# battery_controller.net
KiCad netlist of a schematic drawn in EAGLE
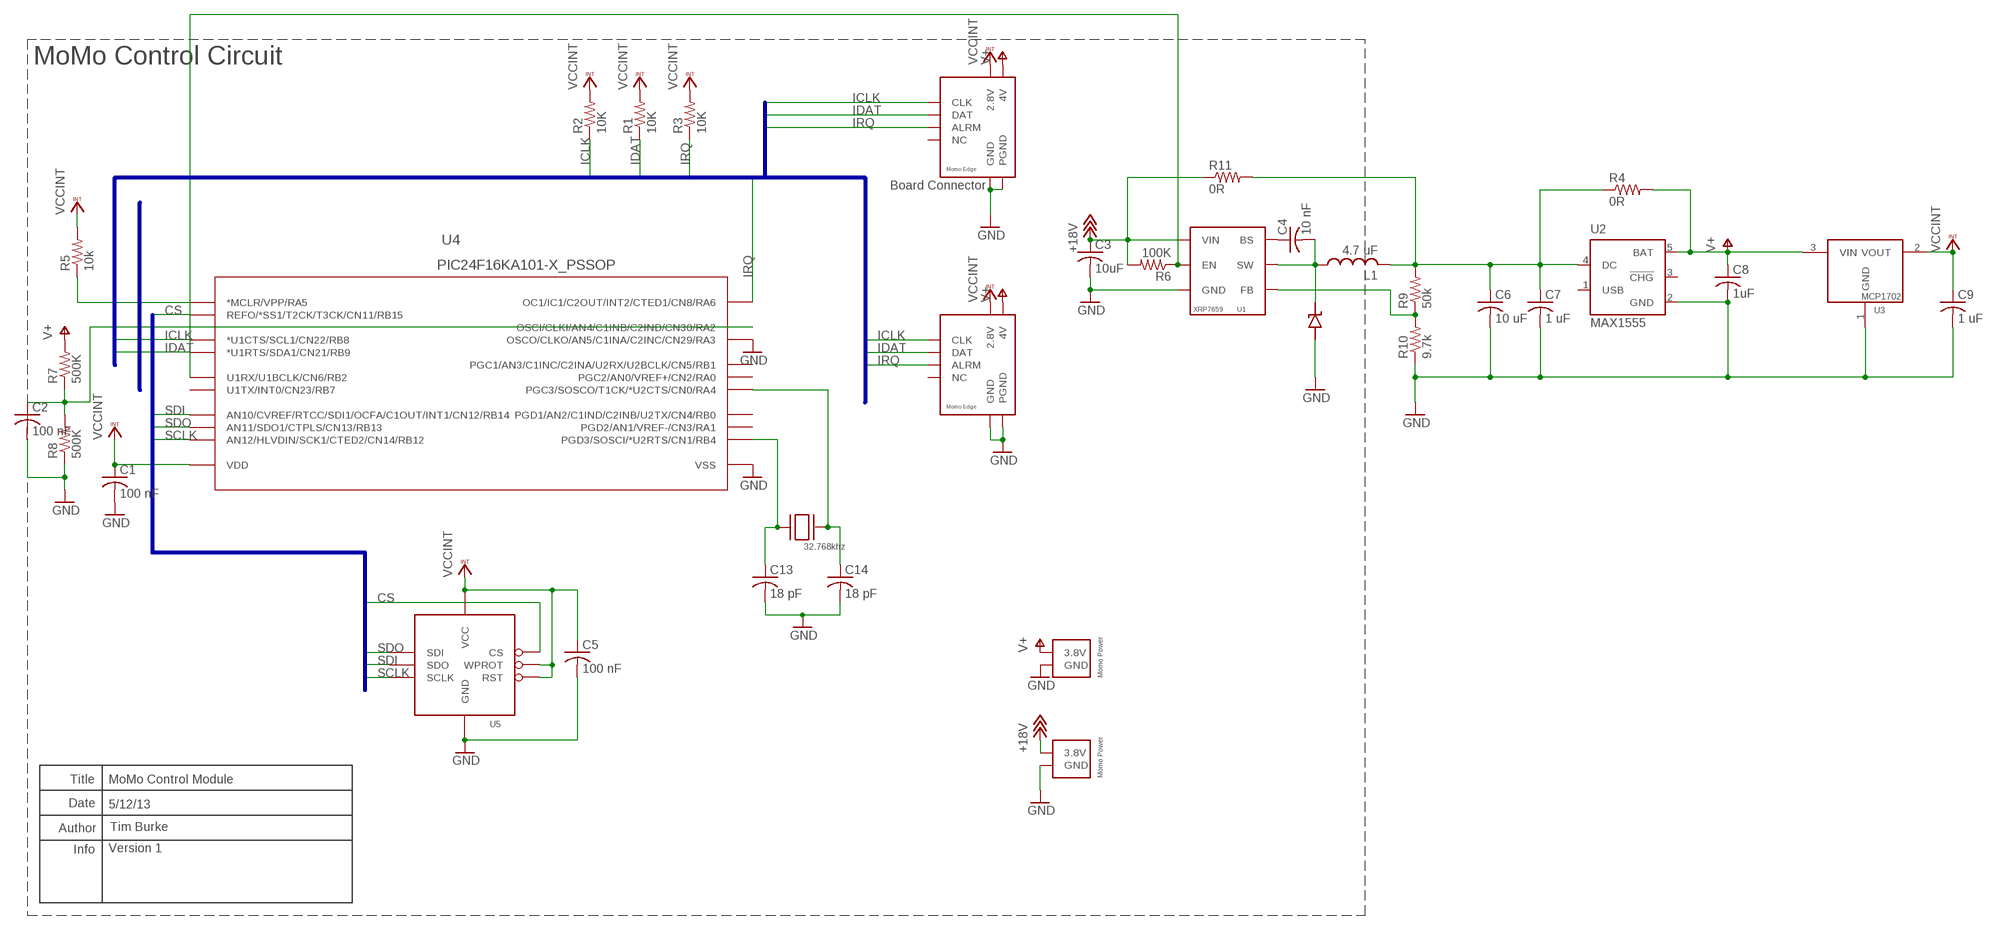
[diagram p0: schematic, sheet 1]

(export (version "E")
  (design (tool "Eeschema 10.0.6"))
  (components
    (comp (ref "C1")
      (value "100 nF")
      (footprint "eagle-import:C0402")
      (libsource (lib "eagle-import") (part "C-USC0402"))
    )
    (comp (ref "C2")
      (value "100 nF")
      (footprint "eagle-import:C0402")
      (libsource (lib "eagle-import") (part "C-USC0402"))
    )
    (comp (ref "C3")
      (value "10uF")
      (footprint "eagle-import:C0805")
      (libsource (lib "eagle-import") (part "C-USC0805"))
    )
    (comp (ref "C4")
      (value "10 nF")
      (footprint "eagle-import:C0402")
      (libsource (lib "eagle-import") (part "C-USC0402"))
    )
    (comp (ref "C5")
      (value "100 nF")
      (footprint "eagle-import:C0402")
      (libsource (lib "eagle-import") (part "C-USC0402"))
    )
    (comp (ref "C6")
      (value "10 uF")
      (footprint "eagle-import:C0805")
      (libsource (lib "eagle-import") (part "C-USC0805"))
    )
    (comp (ref "C7")
      (value "1 uF")
      (footprint "eagle-import:C0402")
      (libsource (lib "eagle-import") (part "C-USC0402"))
    )
    (comp (ref "C8")
      (value "1uF")
      (footprint "eagle-import:C0402")
      (libsource (lib "eagle-import") (part "C-USC0402"))
    )
    (comp (ref "C9")
      (value "1 uF")
      (footprint "eagle-import:C0402")
      (libsource (lib "eagle-import") (part "C-USC0402"))
    )
    (comp (ref "C13")
      (value "18 pF")
      (footprint "eagle-import:C0402K")
      (libsource (lib "eagle-import") (part "C-USC0402K"))
    )
    (comp (ref "C14")
      (value "18 pF")
      (footprint "eagle-import:C0402K")
      (libsource (lib "eagle-import") (part "C-USC0402K"))
    )
    (comp (ref "D1")
      (value "DIODE_SS2P3SS2P3")
      (footprint "eagle-import:DIODE_SS2P3")
      (libsource (lib "eagle-import") (part "DIODE_SS2P3SS2P3"))
    )
    (comp (ref "JP1")
      (value "MOMO-VERT-8M")
      (footprint "eagle-import:1X08")
      (libsource (lib "eagle-import") (part "MOMO-VERT-8M"))
    )
    (comp (ref "JP3")
      (value "MOMO-EDGE-8F")
      (footprint "eagle-import:MOMO-EDGE-8F")
      (libsource (lib "eagle-import") (part "MOMO-EDGE-8F"))
    )
    (comp (ref "L1")
      (value "4.7 uF")
      (footprint "eagle-import:NR6028-INDUCTOR")
      (libsource (lib "eagle-import") (part "NR6028-INDUCTOR"))
    )
    (comp (ref "R1")
      (value "10K")
      (footprint "eagle-import:R0603")
      (libsource (lib "eagle-import") (part "R-US_R0603"))
    )
    (comp (ref "R2")
      (value "10K")
      (footprint "eagle-import:R0603")
      (libsource (lib "eagle-import") (part "R-US_R0603"))
    )
    (comp (ref "R3")
      (value "10K")
      (footprint "eagle-import:R0603")
      (libsource (lib "eagle-import") (part "R-US_R0603"))
    )
    (comp (ref "R4")
      (value "0R")
      (footprint "eagle-import:R0603")
      (libsource (lib "eagle-import") (part "R-US_R0603"))
    )
    (comp (ref "R5")
      (value "10k")
      (footprint "eagle-import:R0402")
      (libsource (lib "eagle-import") (part "R-US_R0402"))
    )
    (comp (ref "R6")
      (value "100K")
      (footprint "eagle-import:R0603")
      (libsource (lib "eagle-import") (part "R-US_R0603"))
    )
    (comp (ref "R7")
      (value "500K")
      (footprint "eagle-import:R0603")
      (libsource (lib "eagle-import") (part "R-US_R0603"))
    )
    (comp (ref "R8")
      (value "500K")
      (footprint "eagle-import:R0603")
      (libsource (lib "eagle-import") (part "R-US_R0603"))
    )
    (comp (ref "R9")
      (value "50k")
      (footprint "eagle-import:R0603")
      (libsource (lib "eagle-import") (part "R-US_R0603"))
    )
    (comp (ref "R10")
      (value "9.7k")
      (footprint "eagle-import:R0603")
      (libsource (lib "eagle-import") (part "R-US_R0603"))
    )
    (comp (ref "R11")
      (value "0R")
      (footprint "eagle-import:R0603")
      (libsource (lib "eagle-import") (part "R-US_R0603"))
    )
    (comp (ref "U$1")
      (value "MOMO-EDGE-POWER-M")
      (footprint "eagle-import:MOMO-EDGE-SMALL-2M")
      (libsource (lib "eagle-import") (part "MOMO-EDGE-POWER-M"))
    )
    (comp (ref "U$2")
      (value "MOMO-EDGE-POWER-M")
      (footprint "eagle-import:MOMO-EDGE-SMALL-2M")
      (libsource (lib "eagle-import") (part "MOMO-EDGE-POWER-M"))
    )
    (comp (ref "U1")
      (value "XRP7659")
      (footprint "eagle-import:SOT23-6L")
      (libsource (lib "eagle-import") (part "XRP7659"))
    )
    (comp (ref "U2")
      (value "MAX1555")
      (footprint "eagle-import:SOT23-5L")
      (fields (field (name "MF") "MAXIM") (field (name "MPN") "MAX1555EZK+T"))
      (libsource (lib "eagle-import") (part "MAX1555"))
    )
    (comp (ref "U3")
      (value "MCP1702")
      (footprint "eagle-import:SOT23")
      (libsource (lib "eagle-import") (part "MCP1702"))
    )
    (comp (ref "U4")
      (value "PIC24F16KA101-X_PSSOP")
      (footprint "eagle-import:SSOP20")
      (libsource (lib "eagle-import") (part "PIC24F16KA101-X_PSSOP"))
    )
    (comp (ref "U5")
      (value "FLASH8MSOP8")
      (footprint "eagle-import:SOP08")
      (libsource (lib "eagle-import") (part "FLASH8MSOP8"))
    )
    (comp (ref "XTAL1")
      (value "32.768khz")
      (footprint "eagle-import:1206")
      (libsource (lib "eagle-import") (part "SMD-XTAL"))
    )
  )
  (nets
    (net (code "1") (name "+18V") (class "Default")
      (node (ref "C3") (pin "1") (pinfunction "1_1") (pintype "passive"))
      (node (ref "R11") (pin "1") (pinfunction "1_1") (pintype "passive"))
      (node (ref "R6") (pin "2") (pinfunction "2_2") (pintype "passive"))
      (node (ref "U$1") (pin "2") (pinfunction "3.8V_2") (pintype "power_in"))
      (node (ref "U1") (pin "5") (pinfunction "VIN_5") (pintype "bidirectional"))
    )
    (net (code "2") (name "/CS") (class "Default")
      (node (ref "U4") (pin "18") (pinfunction "REFO/*SS1/T2CK/T3CK/CN11/RB15_18") (pintype "bidirectional"))
      (node (ref "U5") (pin "1") (pinfunction "CS_1") (pintype "bidirectional"))
    )
    (net (code "3") (name "/ICLK") (class "Default")
      (node (ref "JP1") (pin "3") (pinfunction "CLK_3") (pintype "bidirectional"))
      (node (ref "JP3") (pin "CLK") (pinfunction "CLK_CLK") (pintype "bidirectional"))
      (node (ref "R2") (pin "1") (pinfunction "1_1") (pintype "passive"))
      (node (ref "U4") (pin "12") (pinfunction "*U1CTS/SCL1/CN22/RB8_12") (pintype "bidirectional"))
    )
    (net (code "4") (name "/IDAT") (class "Default")
      (node (ref "JP1") (pin "4") (pinfunction "DAT_4") (pintype "bidirectional"))
      (node (ref "JP3") (pin "DAT") (pinfunction "DAT_DAT") (pintype "bidirectional"))
      (node (ref "R1") (pin "1") (pinfunction "1_1") (pintype "passive"))
      (node (ref "U4") (pin "13") (pinfunction "*U1RTS/SDA1/CN21/RB9_13") (pintype "bidirectional"))
    )
    (net (code "5") (name "/IRQ") (class "Default")
      (node (ref "JP1") (pin "5") (pinfunction "ALRM_5") (pintype "bidirectional"))
      (node (ref "JP3") (pin "ARLM") (pinfunction "ALRM_ARLM") (pintype "bidirectional"))
      (node (ref "R3") (pin "1") (pinfunction "1_1") (pintype "passive"))
      (node (ref "U4") (pin "14") (pinfunction "OC1/IC1/C2OUT/INT2/CTED1/CN8/RA6_14") (pintype "bidirectional"))
    )
    (net (code "6") (name "/SCLK") (class "Default")
      (node (ref "U4") (pin "15") (pinfunction "AN12/HLVDIN/SCK1/CTED2/CN14/RB12_15") (pintype "bidirectional"))
      (node (ref "U5") (pin "6") (pinfunction "SCLK_6") (pintype "bidirectional"))
    )
    (net (code "7") (name "/SDI") (class "Default")
      (node (ref "U4") (pin "17") (pinfunction "AN10/CVREF/RTCC/SDI1/OCFA/C1OUT/INT1/CN12/RB14_17") (pintype "bidirectional"))
      (node (ref "U5") (pin "2") (pinfunction "SDO_2") (pintype "bidirectional"))
    )
    (net (code "8") (name "/SDO") (class "Default")
      (node (ref "U4") (pin "16") (pinfunction "AN11/SDO1/CTPLS/CN13/RB13_16") (pintype "bidirectional"))
      (node (ref "U5") (pin "5") (pinfunction "SDI_5") (pintype "bidirectional"))
    )
    (net (code "9") (name "GND") (class "Default")
      (node (ref "C1") (pin "2") (pinfunction "2_2") (pintype "passive"))
      (node (ref "C13") (pin "2") (pinfunction "2_2") (pintype "passive"))
      (node (ref "C14") (pin "2") (pinfunction "2_2") (pintype "passive"))
      (node (ref "C2") (pin "2") (pinfunction "2_2") (pintype "passive"))
      (node (ref "C3") (pin "2") (pinfunction "2_2") (pintype "passive"))
      (node (ref "C5") (pin "2") (pinfunction "2_2") (pintype "passive"))
      (node (ref "C6") (pin "2") (pinfunction "2_2") (pintype "passive"))
      (node (ref "C7") (pin "2") (pinfunction "2_2") (pintype "passive"))
      (node (ref "C8") (pin "2") (pinfunction "2_2") (pintype "passive"))
      (node (ref "C9") (pin "2") (pinfunction "2_2") (pintype "passive"))
      (node (ref "D1") (pin "AN") (pinfunction "AN_AN") (pintype "bidirectional"))
      (node (ref "JP1") (pin "6") (pinfunction "GND_6") (pintype "power_in"))
      (node (ref "JP1") (pin "8") (pinfunction "PGND_8") (pintype "power_in"))
      (node (ref "JP3") (pin "GND") (pinfunction "GND_GND") (pintype "power_in"))
      (node (ref "JP3") (pin "PGND") (pinfunction "PGND_PGND") (pintype "power_in"))
      (node (ref "R10") (pin "1") (pinfunction "1_1") (pintype "passive"))
      (node (ref "R8") (pin "1") (pinfunction "1_1") (pintype "passive"))
      (node (ref "U$1") (pin "1") (pinfunction "GND_1") (pintype "power_in"))
      (node (ref "U$2") (pin "1") (pinfunction "GND_1") (pintype "power_in"))
      (node (ref "U1") (pin "2") (pinfunction "GND_2") (pintype "bidirectional"))
      (node (ref "U2") (pin "2") (pinfunction "GND_2") (pintype "power_in"))
      (node (ref "U3") (pin "1") (pinfunction "GND_1") (pintype "bidirectional"))
      (node (ref "U4") (pin "19") (pinfunction "VSS_19") (pintype "power_in"))
      (node (ref "U4") (pin "8") (pinfunction "OSCO/CLKO/AN5/C1INA/C2INC/CN29/RA3_8") (pintype "bidirectional"))
      (node (ref "U5") (pin "4") (pinfunction "GND_4") (pintype "power_in"))
    )
    (net (code "10") (name "Net-(U1-BS)") (class "Default")
      (node (ref "C4") (pin "1") (pinfunction "1_1") (pintype "passive"))
      (node (ref "U1") (pin "1") (pinfunction "BS_1") (pintype "bidirectional"))
    )
    (net (code "11") (name "Net-(U1-EN)") (class "Default")
      (node (ref "R6") (pin "1") (pinfunction "1_1") (pintype "passive"))
      (node (ref "U1") (pin "4") (pinfunction "EN_4") (pintype "bidirectional"))
      (node (ref "U4") (pin "6") (pinfunction "U1RX/U1BCLK/CN6/RB2_6") (pintype "bidirectional"))
    )
    (net (code "12") (name "Net-(U1-FB)") (class "Default")
      (node (ref "R10") (pin "2") (pinfunction "2_2") (pintype "passive"))
      (node (ref "R9") (pin "1") (pinfunction "1_1") (pintype "passive"))
      (node (ref "U1") (pin "3") (pinfunction "FB_3") (pintype "bidirectional"))
    )
    (net (code "13") (name "Net-(U1-SW)") (class "Default")
      (node (ref "C4") (pin "2") (pinfunction "2_2") (pintype "passive"))
      (node (ref "D1") (pin "CATH") (pinfunction "CATH_CATH") (pintype "bidirectional"))
      (node (ref "L1") (pin "1") (pinfunction "1_1") (pintype "passive"))
      (node (ref "U1") (pin "6") (pinfunction "SW_6") (pintype "bidirectional"))
    )
    (net (code "14") (name "Net-(U2-DC)") (class "Default")
      (node (ref "C6") (pin "1") (pinfunction "1_1") (pintype "passive"))
      (node (ref "C7") (pin "1") (pinfunction "1_1") (pintype "passive"))
      (node (ref "L1") (pin "2") (pinfunction "2_2") (pintype "passive"))
      (node (ref "R11") (pin "2") (pinfunction "2_2") (pintype "passive"))
      (node (ref "R4") (pin "1") (pinfunction "1_1") (pintype "passive"))
      (node (ref "R9") (pin "2") (pinfunction "2_2") (pintype "passive"))
      (node (ref "U2") (pin "4") (pinfunction "DC_4") (pintype "input"))
    )
    (net (code "15") (name "Net-(U4-*MCLR{slash}VPP{slash}RA5)") (class "Default")
      (node (ref "R5") (pin "1") (pinfunction "1_1") (pintype "passive"))
      (node (ref "U4") (pin "1") (pinfunction "*MCLR/VPP/RA5_1") (pintype "bidirectional"))
    )
    (net (code "16") (name "Net-(U4-OSCI{slash}CLKI{slash}AN4{slash}C1INB{slash}C2IND{slash}CN30{slash}RA2)") (class "Default")
      (node (ref "C2") (pin "1") (pinfunction "1_1") (pintype "passive"))
      (node (ref "R7") (pin "1") (pinfunction "1_1") (pintype "passive"))
      (node (ref "R8") (pin "2") (pinfunction "2_2") (pintype "passive"))
      (node (ref "U4") (pin "7") (pinfunction "OSCI/CLKI/AN4/C1INB/C2IND/CN30/RA2_7") (pintype "bidirectional"))
    )
    (net (code "17") (name "Net-(U4-PGC3{slash}SOSCO{slash}T1CK{slash}*U2CTS{slash}CN0{slash}RA4)") (class "Default")
      (node (ref "C14") (pin "1") (pinfunction "1_1") (pintype "passive"))
      (node (ref "U4") (pin "10") (pinfunction "PGC3/SOSCO/T1CK/*U2CTS/CN0/RA4_10") (pintype "bidirectional"))
      (node (ref "XTAL1") (pin "P$2") (pinfunction "XTAL2_P$2") (pintype "bidirectional"))
    )
    (net (code "18") (name "Net-(U4-PGD3{slash}SOSCI{slash}*U2RTS{slash}CN1{slash}RB4)") (class "Default")
      (node (ref "C13") (pin "1") (pinfunction "1_1") (pintype "passive"))
      (node (ref "U4") (pin "9") (pinfunction "PGD3/SOSCI/*U2RTS/CN1/RB4_9") (pintype "bidirectional"))
      (node (ref "XTAL1") (pin "P$1") (pinfunction "XTAL1_P$1") (pintype "bidirectional"))
    )
    (net (code "19") (name "V+") (class "Default")
      (node (ref "C8") (pin "1") (pinfunction "1_1") (pintype "passive"))
      (node (ref "JP1") (pin "7") (pinfunction "4V_7") (pintype "power_in"))
      (node (ref "JP3") (pin "V4.") (pinfunction "4V_V4.") (pintype "power_in"))
      (node (ref "R4") (pin "2") (pinfunction "2_2") (pintype "passive"))
      (node (ref "R7") (pin "2") (pinfunction "2_2") (pintype "passive"))
      (node (ref "U$2") (pin "2") (pinfunction "3.8V_2") (pintype "power_in"))
      (node (ref "U2") (pin "5") (pinfunction "BAT_5") (pintype "passive"))
      (node (ref "U3") (pin "3") (pinfunction "VIN_3") (pintype "bidirectional"))
    )
    (net (code "20") (name "VCCINT") (class "Default")
      (node (ref "C1") (pin "1") (pinfunction "1_1") (pintype "passive"))
      (node (ref "C5") (pin "1") (pinfunction "1_1") (pintype "passive"))
      (node (ref "C9") (pin "1") (pinfunction "1_1") (pintype "passive"))
      (node (ref "JP1") (pin "1") (pinfunction "2.8V_1") (pintype "power_in"))
      (node (ref "JP3") (pin "V28") (pinfunction "2.8V_V28") (pintype "power_in"))
      (node (ref "R1") (pin "2") (pinfunction "2_2") (pintype "passive"))
      (node (ref "R2") (pin "2") (pinfunction "2_2") (pintype "passive"))
      (node (ref "R3") (pin "2") (pinfunction "2_2") (pintype "passive"))
      (node (ref "R5") (pin "2") (pinfunction "2_2") (pintype "passive"))
      (node (ref "U3") (pin "2") (pinfunction "VOUT_2") (pintype "bidirectional"))
      (node (ref "U4") (pin "20") (pinfunction "VDD_20") (pintype "power_in"))
      (node (ref "U5") (pin "3") (pinfunction "WPROT_3") (pintype "bidirectional"))
      (node (ref "U5") (pin "7") (pinfunction "RST_7") (pintype "bidirectional"))
      (node (ref "U5") (pin "8") (pinfunction "VCC_8") (pintype "power_in"))
    )
    (net (code "21") (name "unconnected-(JP1-NC-Pad2)") (class "Default")
      (node (ref "JP1") (pin "2") (pinfunction "NC_2") (pintype "bidirectional"))
    )
    (net (code "22") (name "unconnected-(JP3-NC-PadNV)") (class "Default")
      (node (ref "JP3") (pin "NV") (pinfunction "NC_NV") (pintype "bidirectional"))
    )
    (net (code "23") (name "unconnected-(U2-USB-Pad1)") (class "Default")
      (node (ref "U2") (pin "1") (pinfunction "USB_1") (pintype "input"))
    )
    (net (code "24") (name "unconnected-(U2-~{CHG}-Pad3)") (class "Default")
      (node (ref "U2") (pin "3") (pinfunction "~{CHG}_3") (pintype "output"))
    )
    (net (code "25") (name "unconnected-(U4-PGC1{slash}AN3{slash}C1INC{slash}C2INA{slash}U2RX{slash}U2BCLK{slash}CN5{slash}RB1-Pad5)") (class "Default")
      (node (ref "U4") (pin "5") (pinfunction "PGC1/AN3/C1INC/C2INA/U2RX/U2BCLK/CN5/RB1_5") (pintype "bidirectional"))
    )
    (net (code "26") (name "unconnected-(U4-PGC2{slash}AN0{slash}VREF+{slash}CN2{slash}RA0-Pad2)") (class "Default")
      (node (ref "U4") (pin "2") (pinfunction "PGC2/AN0/VREF+/CN2/RA0_2") (pintype "bidirectional"))
    )
    (net (code "27") (name "unconnected-(U4-PGD1{slash}AN2{slash}C1IND{slash}C2INB{slash}U2TX{slash}CN4{slash}RB0-Pad4)") (class "Default")
      (node (ref "U4") (pin "4") (pinfunction "PGD1/AN2/C1IND/C2INB/U2TX/CN4/RB0_4") (pintype "bidirectional"))
    )
    (net (code "28") (name "unconnected-(U4-PGD2{slash}AN1{slash}VREF-{slash}CN3{slash}RA1-Pad3)") (class "Default")
      (node (ref "U4") (pin "3") (pinfunction "PGD2/AN1/VREF-/CN3/RA1_3") (pintype "bidirectional"))
    )
    (net (code "29") (name "unconnected-(U4-U1TX{slash}INT0{slash}CN23{slash}RB7-Pad11)") (class "Default")
      (node (ref "U4") (pin "11") (pinfunction "U1TX/INT0/CN23/RB7_11") (pintype "bidirectional"))
    )
  )
)
